# 03_-_LED7SEC.net
KiCad netlist of a schematic drawn in Altium Designer
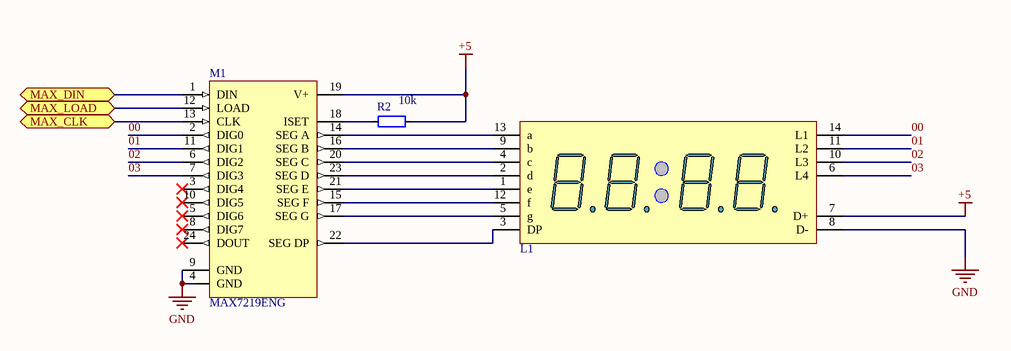
[diagram p0: 03 - LED7SEC.SchDoc]

(export (version "E")
  (design (tool "Eeschema 10.0.6"))
  (components
    (comp (ref "L1")
      (value "Led 7 Seg 4 digit - Anode")
      (footprint "LED7SEG-4-0.56-RG")
      (libsource (lib "My Library.~(1)") (part "LED7SEG-4-RG"))
    )
    (comp (ref "M1")
      (value "MAX7219ENG")
      (footprint "DIP24/W0.3")
      (description "Serially Interfaced, 8-Digit LED Display Driver")
      (fields (field (name "PUBLISHER") "Altium Limited"))
      (libsource (lib "My Library.~(1)") (part "MAX7219ENG"))
    )
    (comp (ref "R2")
      (value "10k")
      (footprint "RES-SMD-0101")
      (description "Resistor")
      (fields
        (field (name "MANUFACTURER") "Generic Components")
        (field (name "PUBLISHER") "Altium Hobart Technology Centre")
      )
      (libsource (lib "My Library.~(5)") (part "Resistor - SMD"))
    )
  )
  (nets
    (net (code "1") (name "+5") (class "Default")
      (node (ref "L1") (pin "7") (pinfunction "D+_7") (pintype "passive"))
      (node (ref "M1") (pin "19") (pinfunction "V+_19") (pintype "power_in"))
      (node (ref "R2") (pin "1") (pinfunction "1_1") (pintype "passive"))
    )
    (net (code "2") (name "/00") (class "Default")
      (node (ref "L1") (pin "14") (pinfunction "L1_14") (pintype "passive"))
      (node (ref "M1") (pin "2") (pinfunction "DIG0_2") (pintype "output"))
    )
    (net (code "3") (name "/01") (class "Default")
      (node (ref "L1") (pin "11") (pinfunction "L2_11") (pintype "passive"))
      (node (ref "M1") (pin "11") (pinfunction "DIG1_11") (pintype "output"))
    )
    (net (code "4") (name "/02") (class "Default")
      (node (ref "L1") (pin "10") (pinfunction "L3_10") (pintype "passive"))
      (node (ref "M1") (pin "6") (pinfunction "DIG2_6") (pintype "output"))
    )
    (net (code "5") (name "/03") (class "Default")
      (node (ref "L1") (pin "6") (pinfunction "L4_6") (pintype "passive"))
      (node (ref "M1") (pin "7") (pinfunction "DIG3_7") (pintype "output"))
    )
    (net (code "6") (name "/MAX_CLK") (class "Default")
      (node (ref "M1") (pin "13") (pinfunction "CLK_13") (pintype "input"))
    )
    (net (code "7") (name "/MAX_DIN") (class "Default")
      (node (ref "M1") (pin "1") (pinfunction "DIN_1") (pintype "input"))
    )
    (net (code "8") (name "/MAX_LOAD") (class "Default")
      (node (ref "M1") (pin "12") (pinfunction "LOAD_12") (pintype "input"))
    )
    (net (code "9") (name "GND") (class "Default")
      (node (ref "L1") (pin "8") (pinfunction "D-_8") (pintype "passive"))
      (node (ref "M1") (pin "4") (pinfunction "GND_4") (pintype "power_in"))
      (node (ref "M1") (pin "9") (pinfunction "GND_9") (pintype "power_in"))
    )
    (net (code "10") (name "Net-(L1-DP)") (class "Default")
      (node (ref "L1") (pin "3") (pinfunction "DP_3") (pintype "passive"))
      (node (ref "M1") (pin "22") (pinfunction "SEG_DP_22") (pintype "output"))
    )
    (net (code "11") (name "Net-(L1-a)") (class "Default")
      (node (ref "L1") (pin "13") (pinfunction "a_13") (pintype "passive"))
      (node (ref "M1") (pin "14") (pinfunction "SEG_A_14") (pintype "output"))
    )
    (net (code "12") (name "Net-(L1-b)") (class "Default")
      (node (ref "L1") (pin "9") (pinfunction "b_9") (pintype "passive"))
      (node (ref "M1") (pin "16") (pinfunction "SEG_B_16") (pintype "output"))
    )
    (net (code "13") (name "Net-(L1-c)") (class "Default")
      (node (ref "L1") (pin "4") (pinfunction "c_4") (pintype "passive"))
      (node (ref "M1") (pin "20") (pinfunction "SEG_C_20") (pintype "output"))
    )
    (net (code "14") (name "Net-(L1-d)") (class "Default")
      (node (ref "L1") (pin "2") (pinfunction "d_2") (pintype "passive"))
      (node (ref "M1") (pin "23") (pinfunction "SEG_D_23") (pintype "output"))
    )
    (net (code "15") (name "Net-(L1-e)") (class "Default")
      (node (ref "L1") (pin "1") (pinfunction "e_1") (pintype "passive"))
      (node (ref "M1") (pin "21") (pinfunction "SEG_E_21") (pintype "output"))
    )
    (net (code "16") (name "Net-(L1-f)") (class "Default")
      (node (ref "L1") (pin "12") (pinfunction "f_12") (pintype "passive"))
      (node (ref "M1") (pin "15") (pinfunction "SEG_F_15") (pintype "output"))
    )
    (net (code "17") (name "Net-(L1-g)") (class "Default")
      (node (ref "L1") (pin "5") (pinfunction "g_5") (pintype "passive"))
      (node (ref "M1") (pin "17") (pinfunction "SEG_G_17") (pintype "output"))
    )
    (net (code "18") (name "Net-(M1-ISET)") (class "Default")
      (node (ref "M1") (pin "18") (pinfunction "ISET_18") (pintype "passive"))
      (node (ref "R2") (pin "2") (pinfunction "2_2") (pintype "passive"))
    )
    (net (code "19") (name "unconnected-(M1-DIG4-Pad3)") (class "Default")
      (node (ref "M1") (pin "3") (pinfunction "DIG4_3") (pintype "output+no_connect"))
    )
    (net (code "20") (name "unconnected-(M1-DIG5-Pad10)") (class "Default")
      (node (ref "M1") (pin "10") (pinfunction "DIG5_10") (pintype "output+no_connect"))
    )
    (net (code "21") (name "unconnected-(M1-DIG6-Pad5)") (class "Default")
      (node (ref "M1") (pin "5") (pinfunction "DIG6_5") (pintype "output+no_connect"))
    )
    (net (code "22") (name "unconnected-(M1-DIG7-Pad8)") (class "Default")
      (node (ref "M1") (pin "8") (pinfunction "DIG7_8") (pintype "output+no_connect"))
    )
    (net (code "23") (name "unconnected-(M1-DOUT-Pad24)") (class "Default")
      (node (ref "M1") (pin "24") (pinfunction "DOUT_24") (pintype "output+no_connect"))
    )
  )
)
